# bt_for_oil.net
KiCad netlist of a schematic drawn in EAGLE
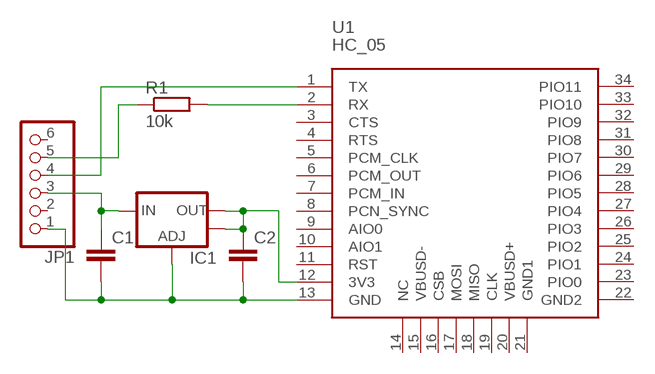
[diagram p0: schematic, sheet 1]

(export (version "E")
  (design (tool "Eeschema 10.0.6"))
  (components
    (comp (ref "C1")
      (value "C-EUC0805")
      (footprint "eagle-import:C0805")
      (libsource (lib "eagle-import") (part "C-EUC0805"))
    )
    (comp (ref "C2")
      (value "C-EUC0805")
      (footprint "eagle-import:C0805")
      (libsource (lib "eagle-import") (part "C-EUC0805"))
    )
    (comp (ref "IC1")
      (value "V_REG_LM1117SOT223")
      (footprint "eagle-import:SOT223")
      (libsource (lib "eagle-import") (part "V_REG_LM1117SOT223"))
    )
    (comp (ref "JP1")
      (value "PINHD-1X6/90")
      (footprint "eagle-import:1X06_90")
      (libsource (lib "eagle-import") (part "PINHD-1X6/90"))
    )
    (comp (ref "R1")
      (value "10k")
      (footprint "eagle-import:M0805")
      (libsource (lib "eagle-import") (part "R-EU_M0805"))
    )
    (comp (ref "U1")
      (value "HC_05")
      (footprint "eagle-import:BLUETOOTH_SMD")
      (libsource (lib "eagle-import") (part "HC_05"))
    )
  )
  (nets
    (net (code "1") (name "Net-(IC1-ADJ)") (class "Default")
      (node (ref "C1") (pin "2") (pinfunction "2_2") (pintype "passive"))
      (node (ref "C2") (pin "2") (pinfunction "2_2") (pintype "passive"))
      (node (ref "IC1") (pin "1") (pinfunction "ADJ_1") (pintype "input"))
      (node (ref "JP1") (pin "1") (pinfunction "1_1") (pintype "passive"))
      (node (ref "U1") (pin "13") (pinfunction "GND_13") (pintype "bidirectional"))
    )
    (net (code "2") (name "Net-(IC1-IN)") (class "Default")
      (node (ref "C1") (pin "1") (pinfunction "1_1") (pintype "passive"))
      (node (ref "IC1") (pin "3") (pinfunction "IN_3") (pintype "input"))
      (node (ref "JP1") (pin "3") (pinfunction "3_3") (pintype "passive"))
    )
    (net (code "3") (name "Net-(JP1-Pad5)") (class "Default")
      (node (ref "JP1") (pin "5") (pinfunction "5_5") (pintype "passive"))
      (node (ref "R1") (pin "1") (pinfunction "1_1") (pintype "passive"))
    )
    (net (code "4") (name "Net-(U1-3V3)") (class "Default")
      (node (ref "C2") (pin "1") (pinfunction "1_1") (pintype "passive"))
      (node (ref "IC1") (pin "2") (pinfunction "OUT_2") (pintype "output"))
      (node (ref "IC1") (pin "4") (pinfunction "OUT_4") (pintype "output"))
      (node (ref "U1") (pin "12") (pinfunction "3V3_12") (pintype "bidirectional"))
    )
    (net (code "5") (name "Net-(U1-RX)") (class "Default")
      (node (ref "R1") (pin "2") (pinfunction "2_2") (pintype "passive"))
      (node (ref "U1") (pin "2") (pinfunction "RX_2") (pintype "bidirectional"))
    )
    (net (code "6") (name "Net-(U1-TX)") (class "Default")
      (node (ref "JP1") (pin "4") (pinfunction "4_4") (pintype "passive"))
      (node (ref "U1") (pin "1") (pinfunction "TX_1") (pintype "bidirectional"))
    )
    (net (code "7") (name "unconnected-(JP1-Pad2)") (class "Default")
      (node (ref "JP1") (pin "2") (pinfunction "2_2") (pintype "passive"))
    )
    (net (code "8") (name "unconnected-(JP1-Pad6)") (class "Default")
      (node (ref "JP1") (pin "6") (pinfunction "6_6") (pintype "passive"))
    )
    (net (code "9") (name "unconnected-(U1-AIO0-Pad9)") (class "Default")
      (node (ref "U1") (pin "9") (pinfunction "AIO0_9") (pintype "bidirectional"))
    )
    (net (code "10") (name "unconnected-(U1-AIO1-Pad10)") (class "Default")
      (node (ref "U1") (pin "10") (pinfunction "AIO1_10") (pintype "bidirectional"))
    )
    (net (code "11") (name "unconnected-(U1-CLK-Pad19)") (class "Default")
      (node (ref "U1") (pin "19") (pinfunction "CLK_19") (pintype "bidirectional"))
    )
    (net (code "12") (name "unconnected-(U1-CSB-Pad16)") (class "Default")
      (node (ref "U1") (pin "16") (pinfunction "CSB_16") (pintype "bidirectional"))
    )
    (net (code "13") (name "unconnected-(U1-CTS-Pad3)") (class "Default")
      (node (ref "U1") (pin "3") (pinfunction "CTS_3") (pintype "bidirectional"))
    )
    (net (code "14") (name "unconnected-(U1-GND1-Pad21)") (class "Default")
      (node (ref "U1") (pin "21") (pinfunction "GND1_21") (pintype "bidirectional"))
    )
    (net (code "15") (name "unconnected-(U1-GND2-Pad22)") (class "Default")
      (node (ref "U1") (pin "22") (pinfunction "GND2_22") (pintype "bidirectional"))
    )
    (net (code "16") (name "unconnected-(U1-MISO-Pad18)") (class "Default")
      (node (ref "U1") (pin "18") (pinfunction "MISO_18") (pintype "bidirectional"))
    )
    (net (code "17") (name "unconnected-(U1-MOSI-Pad17)") (class "Default")
      (node (ref "U1") (pin "17") (pinfunction "MOSI_17") (pintype "bidirectional"))
    )
    (net (code "18") (name "unconnected-(U1-NC-Pad14)") (class "Default")
      (node (ref "U1") (pin "14") (pinfunction "NC_14") (pintype "bidirectional"))
    )
    (net (code "19") (name "unconnected-(U1-PCM_CLK-Pad5)") (class "Default")
      (node (ref "U1") (pin "5") (pinfunction "PCM_CLK_5") (pintype "bidirectional"))
    )
    (net (code "20") (name "unconnected-(U1-PCM_IN-Pad7)") (class "Default")
      (node (ref "U1") (pin "7") (pinfunction "PCM_IN_7") (pintype "bidirectional"))
    )
    (net (code "21") (name "unconnected-(U1-PCM_OUT-Pad6)") (class "Default")
      (node (ref "U1") (pin "6") (pinfunction "PCM_OUT_6") (pintype "bidirectional"))
    )
    (net (code "22") (name "unconnected-(U1-PCN_SYNC-Pad8)") (class "Default")
      (node (ref "U1") (pin "8") (pinfunction "PCN_SYNC_8") (pintype "bidirectional"))
    )
    (net (code "23") (name "unconnected-(U1-PIO0-Pad23)") (class "Default")
      (node (ref "U1") (pin "23") (pinfunction "PIO0_23") (pintype "bidirectional"))
    )
    (net (code "24") (name "unconnected-(U1-PIO1-Pad24)") (class "Default")
      (node (ref "U1") (pin "24") (pinfunction "PIO1_24") (pintype "bidirectional"))
    )
    (net (code "25") (name "unconnected-(U1-PIO2-Pad25)") (class "Default")
      (node (ref "U1") (pin "25") (pinfunction "PIO2_25") (pintype "bidirectional"))
    )
    (net (code "26") (name "unconnected-(U1-PIO3-Pad26)") (class "Default")
      (node (ref "U1") (pin "26") (pinfunction "PIO3_26") (pintype "bidirectional"))
    )
    (net (code "27") (name "unconnected-(U1-PIO4-Pad27)") (class "Default")
      (node (ref "U1") (pin "27") (pinfunction "PIO4_27") (pintype "bidirectional"))
    )
    (net (code "28") (name "unconnected-(U1-PIO5-Pad28)") (class "Default")
      (node (ref "U1") (pin "28") (pinfunction "PIO5_28") (pintype "bidirectional"))
    )
    (net (code "29") (name "unconnected-(U1-PIO6-Pad29)") (class "Default")
      (node (ref "U1") (pin "29") (pinfunction "PIO6_29") (pintype "bidirectional"))
    )
    (net (code "30") (name "unconnected-(U1-PIO7-Pad30)") (class "Default")
      (node (ref "U1") (pin "30") (pinfunction "PIO7_30") (pintype "bidirectional"))
    )
    (net (code "31") (name "unconnected-(U1-PIO8-Pad31)") (class "Default")
      (node (ref "U1") (pin "31") (pinfunction "PIO8_31") (pintype "bidirectional"))
    )
    (net (code "32") (name "unconnected-(U1-PIO9-Pad32)") (class "Default")
      (node (ref "U1") (pin "32") (pinfunction "PIO9_32") (pintype "bidirectional"))
    )
    (net (code "33") (name "unconnected-(U1-PIO10-Pad33)") (class "Default")
      (node (ref "U1") (pin "33") (pinfunction "PIO10_33") (pintype "bidirectional"))
    )
    (net (code "34") (name "unconnected-(U1-PIO11-Pad34)") (class "Default")
      (node (ref "U1") (pin "34") (pinfunction "PIO11_34") (pintype "bidirectional"))
    )
    (net (code "35") (name "unconnected-(U1-RST-Pad11)") (class "Default")
      (node (ref "U1") (pin "11") (pinfunction "RST_11") (pintype "bidirectional"))
    )
    (net (code "36") (name "unconnected-(U1-RTS-Pad4)") (class "Default")
      (node (ref "U1") (pin "4") (pinfunction "RTS_4") (pintype "bidirectional"))
    )
    (net (code "37") (name "unconnected-(U1-VBUSD+-Pad20)") (class "Default")
      (node (ref "U1") (pin "20") (pinfunction "VBUSD+_20") (pintype "bidirectional"))
    )
    (net (code "38") (name "unconnected-(U1-VBUSD--Pad15)") (class "Default")
      (node (ref "U1") (pin "15") (pinfunction "VBUSD-_15") (pintype "bidirectional"))
    )
  )
)
